# SCH_PCB-Hacker-Card_2024-05-22.net
KiCad netlist of a schematic drawn in EasyEDA
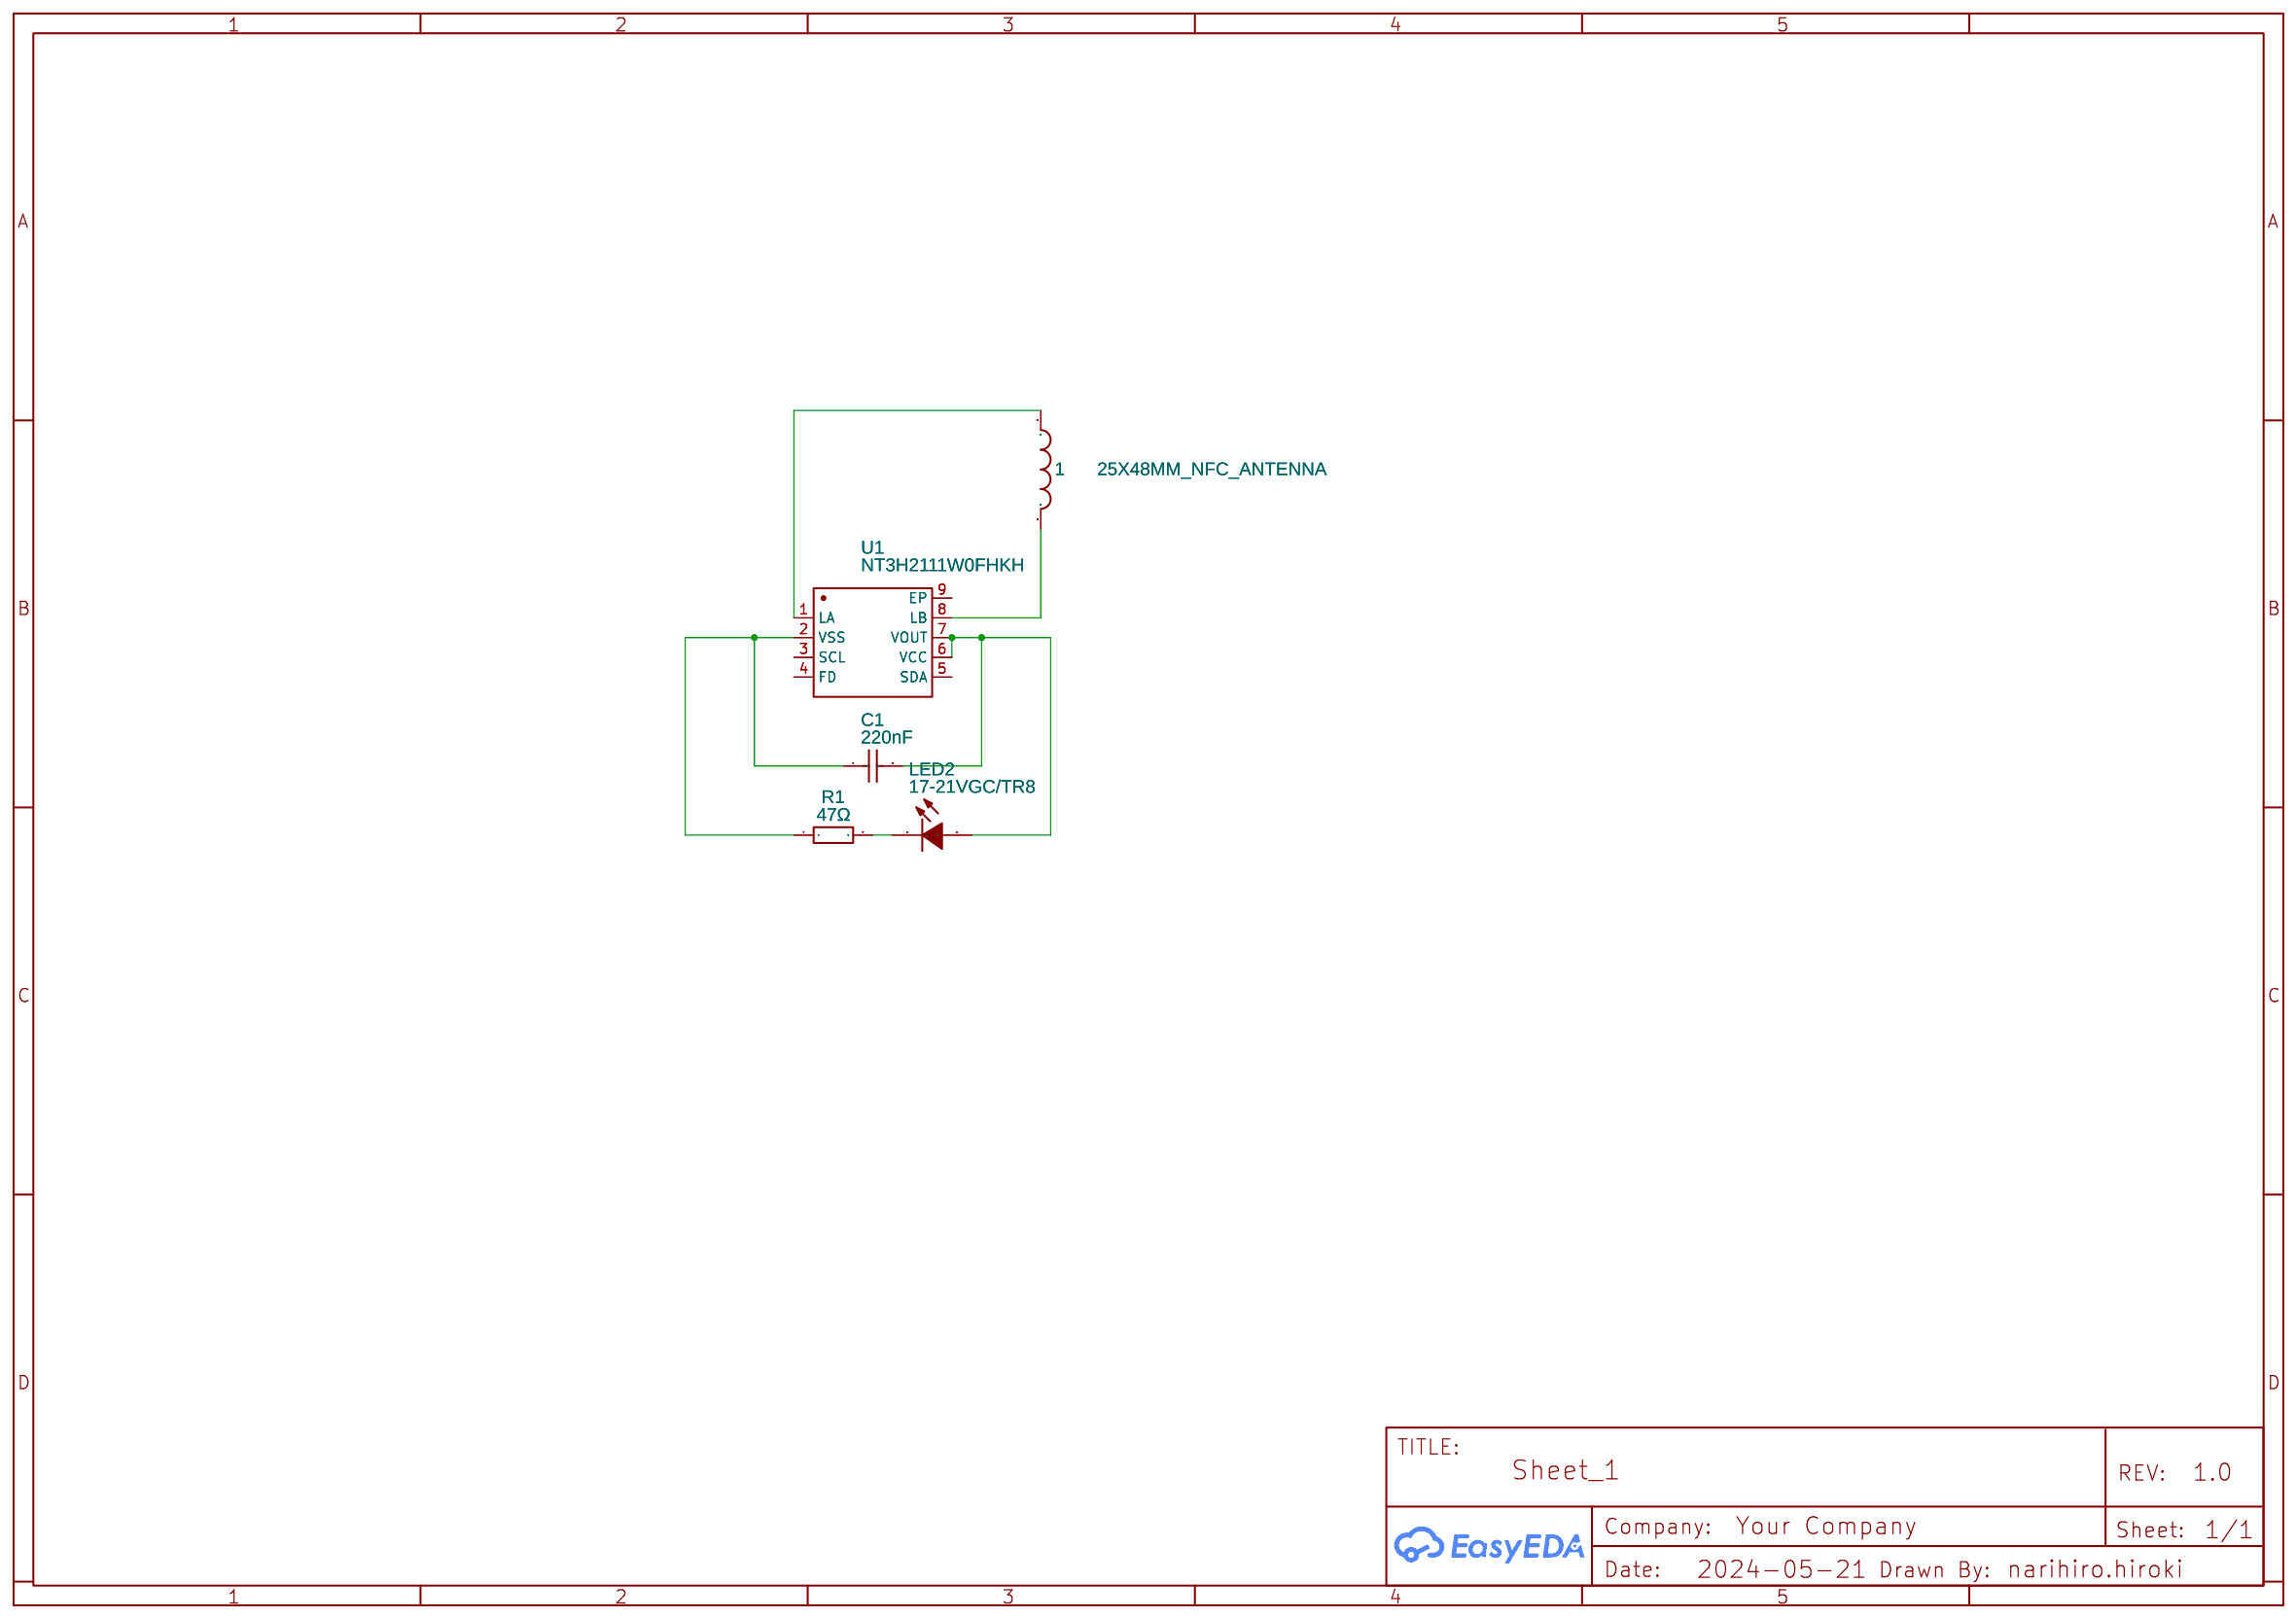
[diagram p0: schematic sheet]

(export (version "E")
  (design (tool "Eeschema 10.0.6"))
  (components
    (comp (ref "1") (value "25X48MM_NFC_ANTENNA") (libsource (lib "") (part "25X48MM_NFC_ANTENNA")))
    (comp (ref "C1")
      (value "220nF")
      (fields
        (field (name "Manufacturer Part") "CL10B224KA8NNNC")
        (field (name "Manufacturer") "SAMSUNG(三星)")
      )
      (libsource (lib "") (part "CL10B224KA8NNNC"))
    )
    (comp (ref "LED2")
      (value "17-21VGC/TR8")
      (fields (field (name "Manufacturer") "EVERLIGHT(亿光)"))
      (libsource (lib "") (part "17-21VGC/TR8"))
    )
    (comp (ref "R1")
      (value "47Ω")
      (fields
        (field (name "Manufacturer Part") "0603WAF470JT5E")
        (field (name "Manufacturer") "UNI-ROYAL(厚声)")
      )
      (libsource (lib "") (part "0603WAF470JT5E"))
    )
    (comp (ref "U1")
      (value "NT3H2111W0FHKH")
      (fields (field (name "Manufacturer") "NXP(恩智浦)"))
      (libsource (lib "") (part "NT3H2111W0FHKH"))
    )
  )
  (nets
    (net (code "1") (name "Net-(LED2-+)") (class "Default")
      (node (ref "C1") (pin "2") (pinfunction "2_2") (pintype "input"))
      (node (ref "LED2") (pin "2") (pinfunction "+_2") (pintype "unspecified"))
      (node (ref "U1") (pin "6") (pinfunction "VCC_6") (pintype "unspecified"))
      (node (ref "U1") (pin "7") (pinfunction "VOUT_7") (pintype "unspecified"))
    )
    (net (code "2") (name "Net-(LED2--)") (class "Default")
      (node (ref "LED2") (pin "1") (pinfunction "-_1") (pintype "unspecified"))
      (node (ref "R1") (pin "2") (pinfunction "2_2") (pintype "input"))
    )
    (net (code "3") (name "Net-(U1-LA)") (class "Default")
      (node (ref "1") (pin "P$1") (pinfunction "P$1_P$1") (pintype "bidirectional"))
      (node (ref "U1") (pin "1") (pinfunction "LA_1") (pintype "unspecified"))
    )
    (net (code "4") (name "Net-(U1-LB)") (class "Default")
      (node (ref "1") (pin "P$2") (pinfunction "P$2_P$2") (pintype "bidirectional"))
      (node (ref "U1") (pin "8") (pinfunction "LB_8") (pintype "unspecified"))
    )
    (net (code "5") (name "Net-(U1-VSS)") (class "Default")
      (node (ref "C1") (pin "1") (pinfunction "1_1") (pintype "input"))
      (node (ref "R1") (pin "1") (pinfunction "1_1") (pintype "input"))
      (node (ref "U1") (pin "2") (pinfunction "VSS_2") (pintype "unspecified"))
    )
    (net (code "6") (name "unconnected-(U1-EP-Pad9)") (class "Default")
      (node (ref "U1") (pin "9") (pinfunction "EP_9") (pintype "unspecified"))
    )
    (net (code "7") (name "unconnected-(U1-FD-Pad4)") (class "Default")
      (node (ref "U1") (pin "4") (pinfunction "FD_4") (pintype "unspecified"))
    )
    (net (code "8") (name "unconnected-(U1-SCL-Pad3)") (class "Default")
      (node (ref "U1") (pin "3") (pinfunction "SCL_3") (pintype "unspecified"))
    )
    (net (code "9") (name "unconnected-(U1-SDA-Pad5)") (class "Default")
      (node (ref "U1") (pin "5") (pinfunction "SDA_5") (pintype "unspecified"))
    )
  )
)
